# HolaBot.net
KiCad netlist of a schematic drawn in EasyEDA
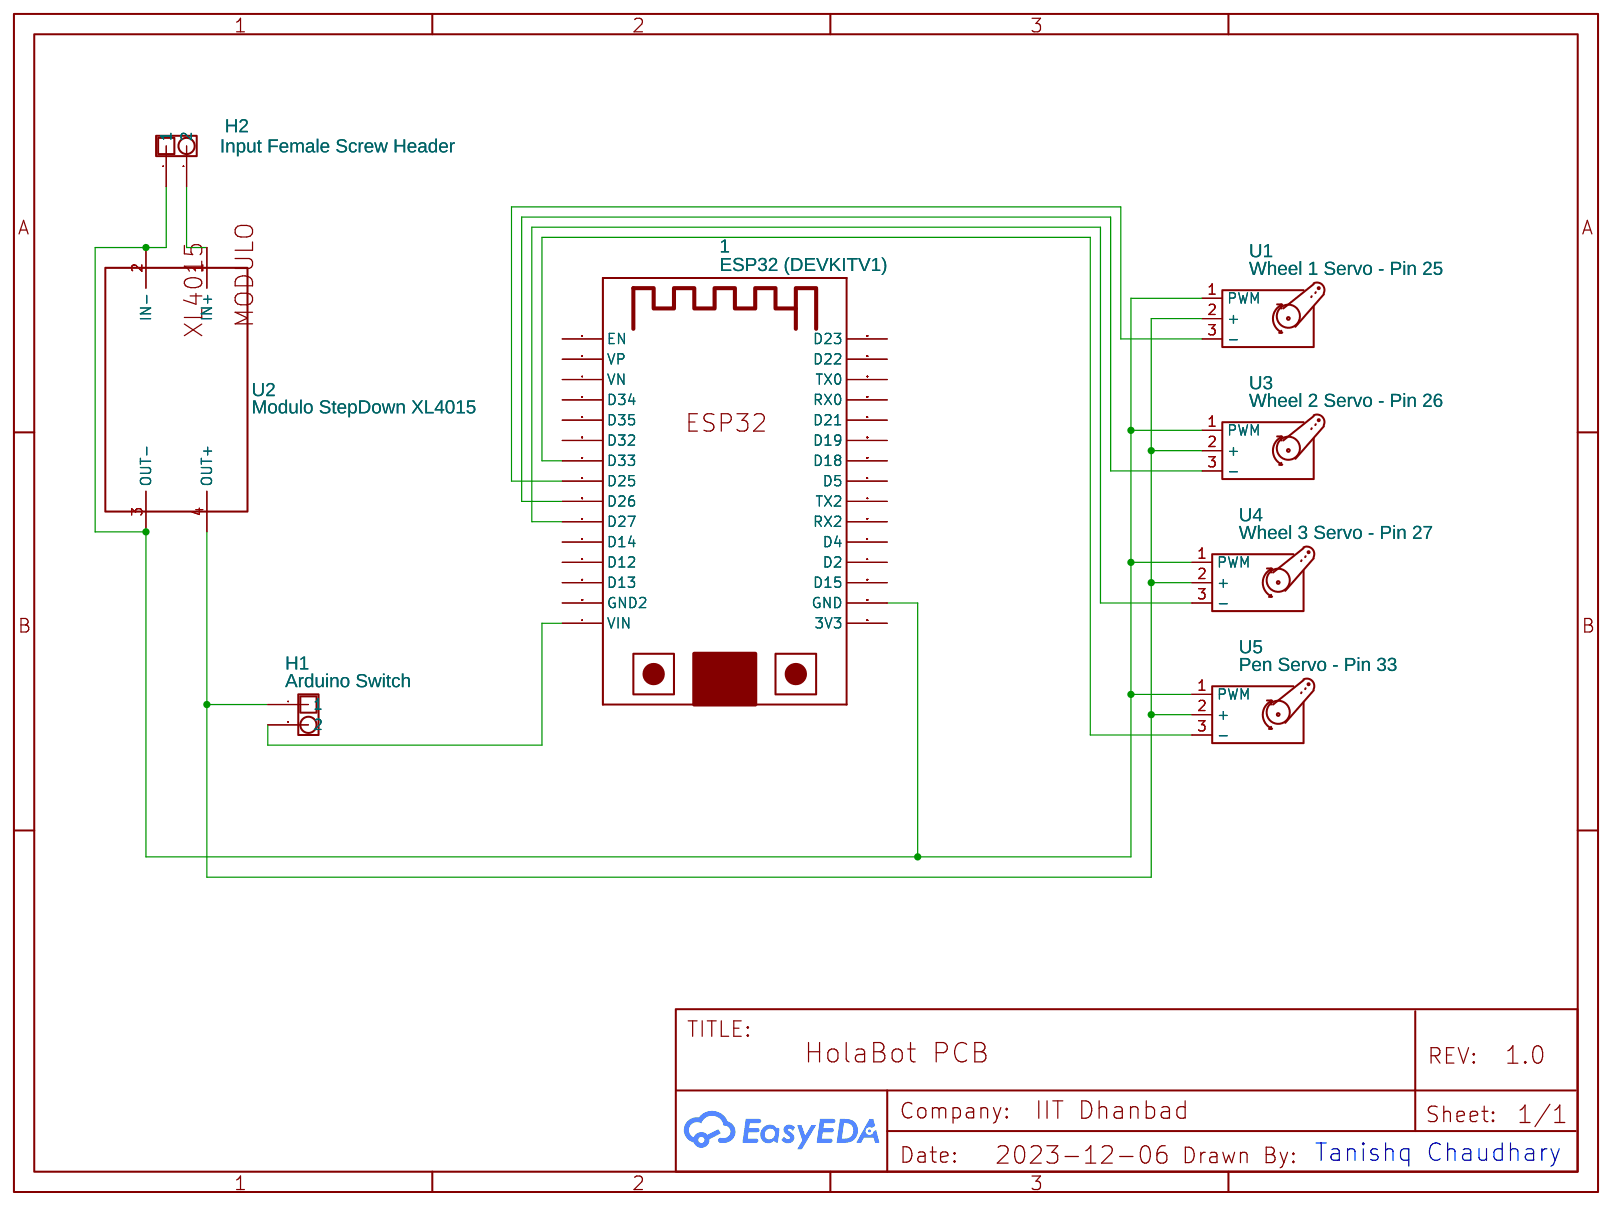
[diagram p0: schematic sheet]

(export (version "E")
  (design (tool "Eeschema 10.0.6"))
  (components
    (comp (ref "1") (value "ESP32 (DEVKITV1)") (libsource (lib "") (part "ESP32-DEVKIT-V1-30PIN")))
    (comp (ref "H1") (value "Arduino Switch") (libsource (lib "") (part "Header pins 1x02 1MM HOLES")))
    (comp (ref "H2")
      (value "Input Female Screw Header")
      (libsource (lib "") (part "Header pins 1x02 1MM HOLES_1"))
    )
    (comp (ref "U1") (value "Wheel 1 Servo - Pin 25") (libsource (lib "") (part "KKTL-MOTOR-SERVO-01 COPY")))
    (comp (ref "U2") (value "Modulo StepDown XL4015") (libsource (lib "") (part "Modulo StepDown XL4015")))
    (comp (ref "U3") (value "Wheel 2 Servo - Pin 26") (libsource (lib "") (part "KKTL-MOTOR-SERVO-01 COPY")))
    (comp (ref "U4") (value "Wheel 3 Servo - Pin 27") (libsource (lib "") (part "KKTL-MOTOR-SERVO-01 COPY")))
    (comp (ref "U5") (value "Pen Servo - Pin 33") (libsource (lib "") (part "KKTL-MOTOR-SERVO-01 COPY")))
  )
  (nets
    (net (code "1") (name "Net-(1-PadVIN)") (class "Default")
      (node (ref "1") (pin "VIN") (pinfunction "VIN_VIN") (pintype "unspecified"))
      (node (ref "H1") (pin "2") (pinfunction "2_2") (pintype "unspecified"))
    )
    (net (code "2") (name "Net-(U1-+)") (class "Default")
      (node (ref "H1") (pin "1") (pinfunction "1_1") (pintype "unspecified"))
      (node (ref "U1") (pin "2") (pinfunction "+_2") (pintype "unspecified"))
      (node (ref "U2") (pin "4") (pinfunction "OUT+_4") (pintype "unspecified"))
      (node (ref "U3") (pin "2") (pinfunction "+_2") (pintype "unspecified"))
      (node (ref "U4") (pin "2") (pinfunction "+_2") (pintype "unspecified"))
      (node (ref "U5") (pin "2") (pinfunction "+_2") (pintype "unspecified"))
    )
    (net (code "3") (name "Net-(U1--)") (class "Default")
      (node (ref "1") (pin "D25") (pinfunction "D25_D25") (pintype "unspecified"))
      (node (ref "U1") (pin "3") (pinfunction "-_3") (pintype "unspecified"))
    )
    (net (code "4") (name "Net-(U1-PWM)") (class "Default")
      (node (ref "1") (pin "GND") (pinfunction "GND_GND") (pintype "unspecified"))
      (node (ref "H2") (pin "1") (pinfunction "1_1") (pintype "unspecified"))
      (node (ref "U1") (pin "1") (pinfunction "PWM_1") (pintype "unspecified"))
      (node (ref "U2") (pin "2") (pinfunction "IN-_2") (pintype "unspecified"))
      (node (ref "U2") (pin "3") (pinfunction "OUT-_3") (pintype "unspecified"))
      (node (ref "U3") (pin "1") (pinfunction "PWM_1") (pintype "unspecified"))
      (node (ref "U4") (pin "1") (pinfunction "PWM_1") (pintype "unspecified"))
      (node (ref "U5") (pin "1") (pinfunction "PWM_1") (pintype "unspecified"))
    )
    (net (code "5") (name "Net-(U2-IN+)") (class "Default")
      (node (ref "H2") (pin "2") (pinfunction "2_2") (pintype "unspecified"))
      (node (ref "U2") (pin "1") (pinfunction "IN+_1") (pintype "unspecified"))
    )
    (net (code "6") (name "Net-(U3--)") (class "Default")
      (node (ref "1") (pin "D26") (pinfunction "D26_D26") (pintype "unspecified"))
      (node (ref "U3") (pin "3") (pinfunction "-_3") (pintype "unspecified"))
    )
    (net (code "7") (name "Net-(U4--)") (class "Default")
      (node (ref "1") (pin "D27") (pinfunction "D27_D27") (pintype "unspecified"))
      (node (ref "U4") (pin "3") (pinfunction "-_3") (pintype "unspecified"))
    )
    (net (code "8") (name "Net-(U5--)") (class "Default")
      (node (ref "1") (pin "D33") (pinfunction "D33_D33") (pintype "unspecified"))
      (node (ref "U5") (pin "3") (pinfunction "-_3") (pintype "unspecified"))
    )
    (net (code "9") (name "unconnected-(1-Pad3V3)") (class "Default")
      (node (ref "1") (pin "3V3") (pinfunction "3V3_3V3") (pintype "unspecified"))
    )
    (net (code "10") (name "unconnected-(1-PadD2)") (class "Default")
      (node (ref "1") (pin "D2") (pinfunction "D2_D2") (pintype "unspecified"))
    )
    (net (code "11") (name "unconnected-(1-PadD4)") (class "Default")
      (node (ref "1") (pin "D4") (pinfunction "D4_D4") (pintype "unspecified"))
    )
    (net (code "12") (name "unconnected-(1-PadD5)") (class "Default")
      (node (ref "1") (pin "D5") (pinfunction "D5_D5") (pintype "unspecified"))
    )
    (net (code "13") (name "unconnected-(1-PadD12)") (class "Default")
      (node (ref "1") (pin "D12") (pinfunction "D12_D12") (pintype "unspecified"))
    )
    (net (code "14") (name "unconnected-(1-PadD13)") (class "Default")
      (node (ref "1") (pin "D13") (pinfunction "D13_D13") (pintype "unspecified"))
    )
    (net (code "15") (name "unconnected-(1-PadD14)") (class "Default")
      (node (ref "1") (pin "D14") (pinfunction "D14_D14") (pintype "unspecified"))
    )
    (net (code "16") (name "unconnected-(1-PadD15)") (class "Default")
      (node (ref "1") (pin "D15") (pinfunction "D15_D15") (pintype "unspecified"))
    )
    (net (code "17") (name "unconnected-(1-PadD18)") (class "Default")
      (node (ref "1") (pin "D18") (pinfunction "D18_D18") (pintype "unspecified"))
    )
    (net (code "18") (name "unconnected-(1-PadD19)") (class "Default")
      (node (ref "1") (pin "D19") (pinfunction "D19_D19") (pintype "unspecified"))
    )
    (net (code "19") (name "unconnected-(1-PadD21)") (class "Default")
      (node (ref "1") (pin "D21") (pinfunction "D21_D21") (pintype "unspecified"))
    )
    (net (code "20") (name "unconnected-(1-PadD22)") (class "Default")
      (node (ref "1") (pin "D22") (pinfunction "D22_D22") (pintype "unspecified"))
    )
    (net (code "21") (name "unconnected-(1-PadD23)") (class "Default")
      (node (ref "1") (pin "D23") (pinfunction "D23_D23") (pintype "unspecified"))
    )
    (net (code "22") (name "unconnected-(1-PadD32)") (class "Default")
      (node (ref "1") (pin "D32") (pinfunction "D32_D32") (pintype "unspecified"))
    )
    (net (code "23") (name "unconnected-(1-PadD34)") (class "Default")
      (node (ref "1") (pin "D34") (pinfunction "D34_D34") (pintype "unspecified"))
    )
    (net (code "24") (name "unconnected-(1-PadD35)") (class "Default")
      (node (ref "1") (pin "D35") (pinfunction "D35_D35") (pintype "unspecified"))
    )
    (net (code "25") (name "unconnected-(1-PadEN)") (class "Default")
      (node (ref "1") (pin "EN") (pinfunction "EN_EN") (pintype "unspecified"))
    )
    (net (code "26") (name "unconnected-(1-PadGND2)") (class "Default")
      (node (ref "1") (pin "GND2") (pinfunction "GND2_GND2") (pintype "unspecified"))
    )
    (net (code "27") (name "unconnected-(1-PadRX0)") (class "Default")
      (node (ref "1") (pin "RX0") (pinfunction "RX0_RX0") (pintype "unspecified"))
    )
    (net (code "28") (name "unconnected-(1-PadRX2)") (class "Default")
      (node (ref "1") (pin "RX2") (pinfunction "RX2_RX2") (pintype "unspecified"))
    )
    (net (code "29") (name "unconnected-(1-PadTX0)") (class "Default")
      (node (ref "1") (pin "TX0") (pinfunction "TX0_TX0") (pintype "unspecified"))
    )
    (net (code "30") (name "unconnected-(1-PadTX2)") (class "Default")
      (node (ref "1") (pin "TX2") (pinfunction "TX2_TX2") (pintype "unspecified"))
    )
    (net (code "31") (name "unconnected-(1-PadVN)") (class "Default")
      (node (ref "1") (pin "VN") (pinfunction "VN_VN") (pintype "unspecified"))
    )
    (net (code "32") (name "unconnected-(1-PadVP)") (class "Default")
      (node (ref "1") (pin "VP") (pinfunction "VP_VP") (pintype "unspecified"))
    )
  )
)
